# 5Wled-mosfet_3.net
KiCad netlist of a schematic drawn in EAGLE
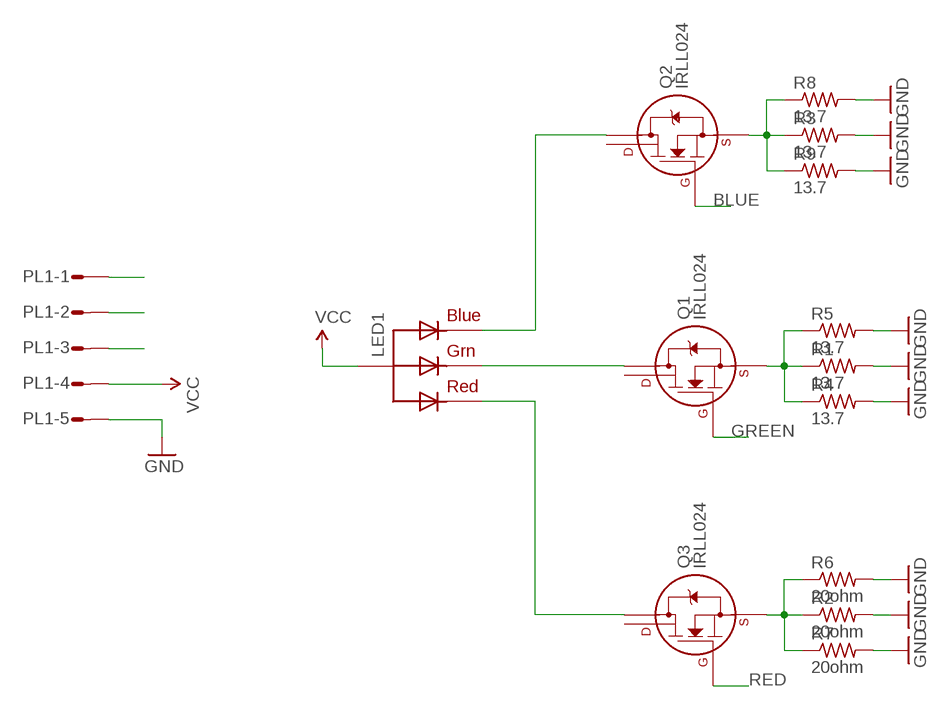
[diagram p0: schematic, sheet 1]

(export (version "E")
  (design (tool "Eeschema 10.0.6"))
  (components
    (comp (ref "LED1")
      (value "RGBLED_CA4.5MM")
      (footprint "eagle-import:5WRGBLED")
      (libsource (lib "eagle-import") (part "RGBLED_CA4.5MM"))
    )
    (comp (ref "PL1")
      (value "DF3-05R")
      (footprint "eagle-import:DF3R-05")
      (libsource (lib "eagle-import") (part "DF3-05R"))
    )
    (comp (ref "Q1")
      (value "IRLL024")
      (footprint "eagle-import:SOT-223")
      (libsource (lib "eagle-import") (part "IRLL024"))
    )
    (comp (ref "Q2")
      (value "IRLL024")
      (footprint "eagle-import:SOT-223")
      (libsource (lib "eagle-import") (part "IRLL024"))
    )
    (comp (ref "Q3")
      (value "IRLL024")
      (footprint "eagle-import:SOT-223")
      (libsource (lib "eagle-import") (part "IRLL024"))
    )
    (comp (ref "R1")
      (value "13.7")
      (footprint "eagle-import:R1210")
      (libsource (lib "eagle-import") (part "R-US_R1210"))
    )
    (comp (ref "R2")
      (value "20ohm")
      (footprint "eagle-import:R1210")
      (libsource (lib "eagle-import") (part "R-US_R1210"))
    )
    (comp (ref "R3")
      (value "13.7")
      (footprint "eagle-import:R1210")
      (libsource (lib "eagle-import") (part "R-US_R1210"))
    )
    (comp (ref "R4")
      (value "13.7")
      (footprint "eagle-import:R1210")
      (libsource (lib "eagle-import") (part "R-US_R1210"))
    )
    (comp (ref "R5")
      (value "13.7")
      (footprint "eagle-import:R1210")
      (libsource (lib "eagle-import") (part "R-US_R1210"))
    )
    (comp (ref "R6")
      (value "20ohm")
      (footprint "eagle-import:R1210")
      (libsource (lib "eagle-import") (part "R-US_R1210"))
    )
    (comp (ref "R7")
      (value "20ohm")
      (footprint "eagle-import:R1210")
      (libsource (lib "eagle-import") (part "R-US_R1210"))
    )
    (comp (ref "R8")
      (value "13.7")
      (footprint "eagle-import:R1210")
      (libsource (lib "eagle-import") (part "R-US_R1210"))
    )
    (comp (ref "R9")
      (value "13.7")
      (footprint "eagle-import:R1210")
      (libsource (lib "eagle-import") (part "R-US_R1210"))
    )
  )
  (nets
    (net (code "1") (name "/BLUE") (class "Default")
      (node (ref "PL1") (pin "3") (pinfunction "S_3") (pintype "passive"))
      (node (ref "Q2") (pin "1") (pinfunction "G_1") (pintype "tri_state"))
    )
    (net (code "2") (name "/GREEN") (class "Default")
      (node (ref "PL1") (pin "1") (pinfunction "S_1") (pintype "passive"))
      (node (ref "Q1") (pin "1") (pinfunction "G_1") (pintype "tri_state"))
    )
    (net (code "3") (name "/RED") (class "Default")
      (node (ref "PL1") (pin "2") (pinfunction "S_2") (pintype "passive"))
      (node (ref "Q3") (pin "1") (pinfunction "G_1") (pintype "tri_state"))
    )
    (net (code "4") (name "GND") (class "Default")
      (node (ref "PL1") (pin "5") (pinfunction "S_5") (pintype "passive"))
      (node (ref "R1") (pin "2") (pinfunction "2_2") (pintype "passive"))
      (node (ref "R2") (pin "2") (pinfunction "2_2") (pintype "passive"))
      (node (ref "R3") (pin "2") (pinfunction "2_2") (pintype "passive"))
      (node (ref "R4") (pin "2") (pinfunction "2_2") (pintype "passive"))
      (node (ref "R5") (pin "2") (pinfunction "2_2") (pintype "passive"))
      (node (ref "R6") (pin "2") (pinfunction "2_2") (pintype "passive"))
      (node (ref "R7") (pin "2") (pinfunction "2_2") (pintype "passive"))
      (node (ref "R8") (pin "2") (pinfunction "2_2") (pintype "passive"))
      (node (ref "R9") (pin "2") (pinfunction "2_2") (pintype "passive"))
    )
    (net (code "5") (name "Net-(LED1-BLUE)") (class "Default")
      (node (ref "LED1") (pin "1") (pinfunction "BLUE_1") (pintype "bidirectional"))
      (node (ref "Q2") (pin "2") (pinfunction "D1_2") (pintype "bidirectional"))
    )
    (net (code "6") (name "Net-(LED1-GREEN)") (class "Default")
      (node (ref "LED1") (pin "3") (pinfunction "GREEN_3") (pintype "bidirectional"))
      (node (ref "Q1") (pin "2") (pinfunction "D1_2") (pintype "bidirectional"))
    )
    (net (code "7") (name "Net-(LED1-RED)") (class "Default")
      (node (ref "LED1") (pin "2") (pinfunction "RED_2") (pintype "bidirectional"))
      (node (ref "Q3") (pin "2") (pinfunction "D1_2") (pintype "bidirectional"))
    )
    (net (code "8") (name "Net-(Q1-S)") (class "Default")
      (node (ref "Q1") (pin "3") (pinfunction "S_3") (pintype "bidirectional"))
      (node (ref "R1") (pin "1") (pinfunction "1_1") (pintype "passive"))
      (node (ref "R4") (pin "1") (pinfunction "1_1") (pintype "passive"))
      (node (ref "R5") (pin "1") (pinfunction "1_1") (pintype "passive"))
    )
    (net (code "9") (name "Net-(Q2-S)") (class "Default")
      (node (ref "Q2") (pin "3") (pinfunction "S_3") (pintype "bidirectional"))
      (node (ref "R3") (pin "1") (pinfunction "1_1") (pintype "passive"))
      (node (ref "R8") (pin "1") (pinfunction "1_1") (pintype "passive"))
      (node (ref "R9") (pin "1") (pinfunction "1_1") (pintype "passive"))
    )
    (net (code "10") (name "Net-(Q3-S)") (class "Default")
      (node (ref "Q3") (pin "3") (pinfunction "S_3") (pintype "bidirectional"))
      (node (ref "R2") (pin "1") (pinfunction "1_1") (pintype "passive"))
      (node (ref "R6") (pin "1") (pinfunction "1_1") (pintype "passive"))
      (node (ref "R7") (pin "1") (pinfunction "1_1") (pintype "passive"))
    )
    (net (code "11") (name "VCC") (class "Default")
      (node (ref "LED1") (pin "4") (pinfunction "VCC_4") (pintype "bidirectional"))
      (node (ref "PL1") (pin "4") (pinfunction "S_4") (pintype "passive"))
    )
    (net (code "12") (name "unconnected-(Q1-D2-Pad4)") (class "Default")
      (node (ref "Q1") (pin "4") (pinfunction "D2_4") (pintype "bidirectional"))
    )
    (net (code "13") (name "unconnected-(Q2-D2-Pad4)") (class "Default")
      (node (ref "Q2") (pin "4") (pinfunction "D2_4") (pintype "bidirectional"))
    )
    (net (code "14") (name "unconnected-(Q3-D2-Pad4)") (class "Default")
      (node (ref "Q3") (pin "4") (pinfunction "D2_4") (pintype "bidirectional"))
    )
  )
)
